# Supply_DDS.net
KiCad netlist of a schematic drawn in Altium Designer
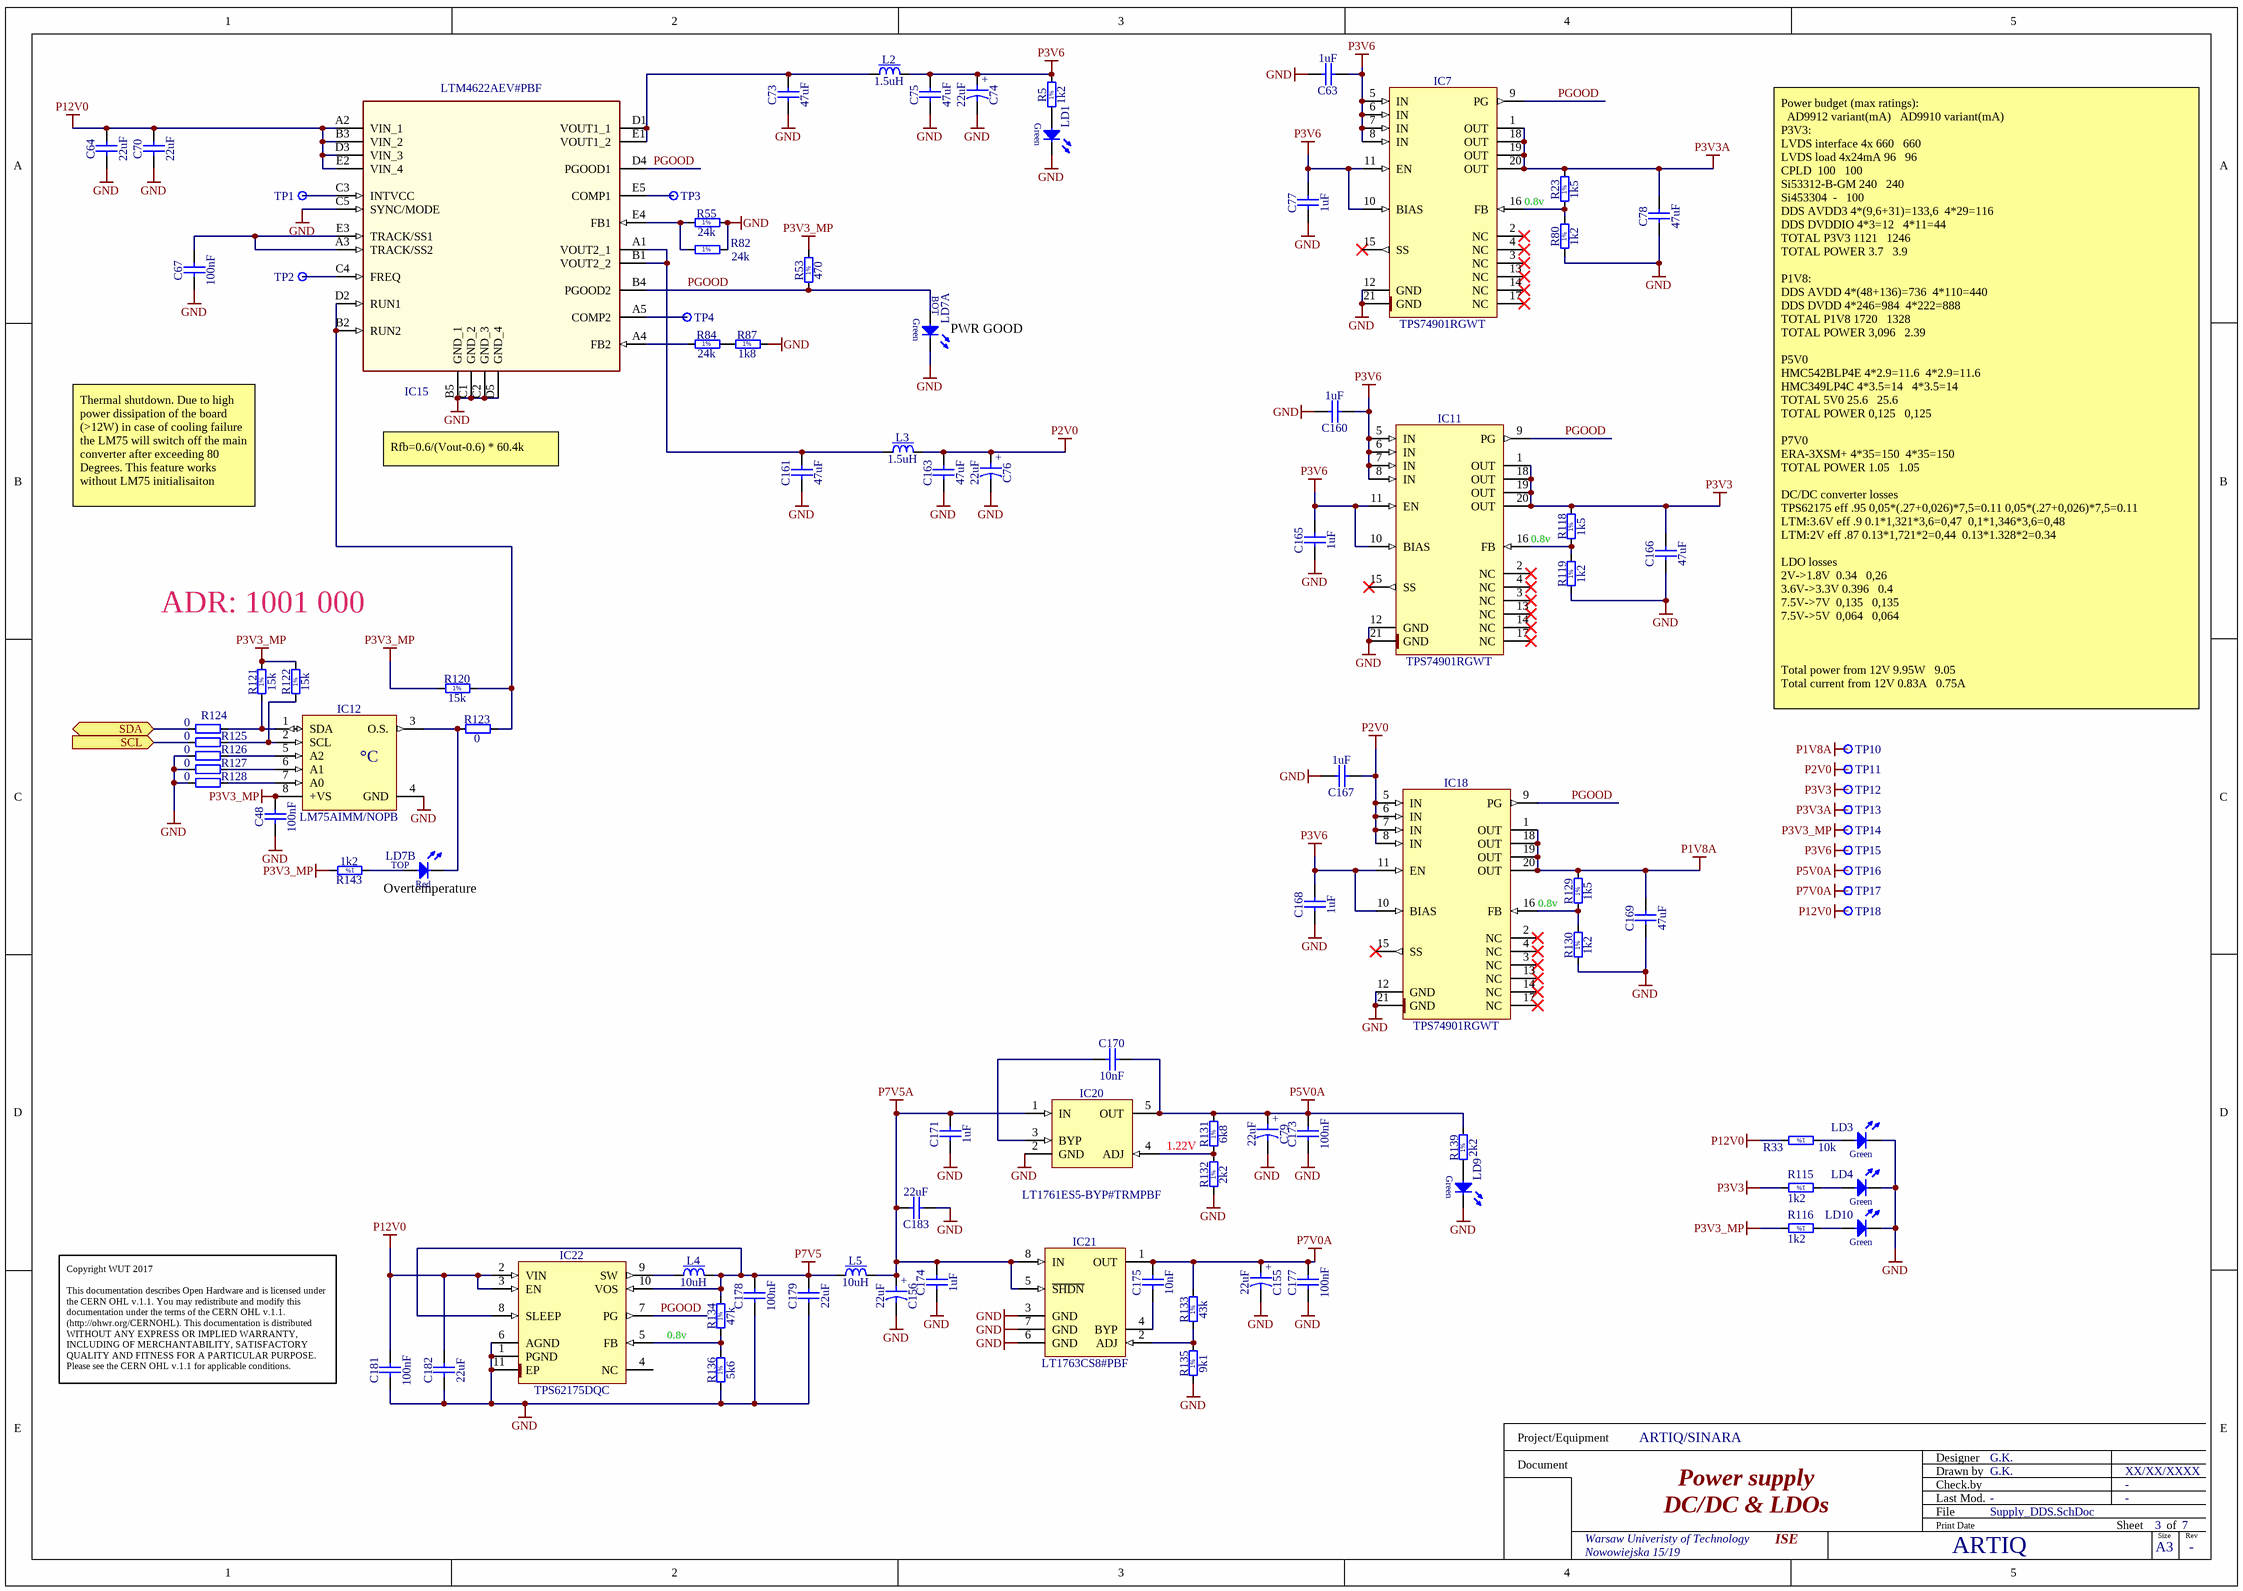
[diagram p0: Supply_DDS.SchDoc]

(export (version "E")
  (design (tool "Eeschema 10.0.6"))
  (components
    (comp (ref "C48")
      (value "100nF")
      (footprint "CAPC1005X55N")
      (description "Non-polarised capacitor")
      (fields (field (name "PART NUMBER") "CC0402_100NF_16V_10%_X5R") (field (name "VOLTAGE") "16V"))
      (libsource (lib "Capacitors") (part "Capacitor - non polarized"))
    )
    (comp (ref "C63")
      (value "1uF")
      (footprint "CAPC1005X55N")
      (description "Non-polarised capacitor")
      (fields (field (name "PART NUMBER") "CC0402_1UF_16V_10%_X5R") (field (name "VOLTAGE") "16V"))
      (libsource (lib "Capacitors") (part "Capacitor - non polarized"))
    )
    (comp (ref "C64")
      (value "22uF")
      (footprint "CAPC2012X135N")
      (description "Non-polarised capacitor")
      (fields (field (name "PART NUMBER") "CC0805_22UF_16V_10%_X5R") (field (name "VOLTAGE") "16V"))
      (libsource (lib "Capacitors") (part "Capacitor - non polarized"))
    )
    (comp (ref "C67")
      (value "100nF")
      (footprint "CAPC1005X55N")
      (description "Non-polarised capacitor")
      (fields (field (name "PART NUMBER") "CC0402_100NF_16V_10%_X5R") (field (name "VOLTAGE") "16V"))
      (libsource (lib "Capacitors") (part "Capacitor - non polarized"))
    )
    (comp (ref "C70")
      (value "22uF")
      (footprint "CAPC2012X135N")
      (description "Non-polarised capacitor")
      (fields (field (name "PART NUMBER") "CC0805_22UF_16V_10%_X5R") (field (name "VOLTAGE") "16V"))
      (libsource (lib "Capacitors") (part "Capacitor - non polarized"))
    )
    (comp (ref "C73")
      (value "47uF")
      (footprint "CAPC3225X270N")
      (description "Non-polarised capacitor")
      (fields (field (name "PART NUMBER") "CC1210_47UF_10V_20%_X5R") (field (name "VOLTAGE") "10V"))
      (libsource (lib "Capacitors") (part "Capacitor - non polarized"))
    )
    (comp (ref "C74")
      (value "22uF")
      (footprint "CAPMP3528X210N")
      (description "Polarised capacitor")
      (fields (field (name "PART NUMBER") "CTE3528-21_22UF_10V_10%_LESR0700") (field (name "VOLTAGE") "10V"))
      (libsource (lib "Capacitors") (part "Capacitor - polarized"))
    )
    (comp (ref "C75")
      (value "47uF")
      (footprint "CAPC3225X270N")
      (description "Non-polarised capacitor")
      (fields (field (name "PART NUMBER") "CC1210_47UF_10V_20%_X5R") (field (name "VOLTAGE") "10V"))
      (libsource (lib "Capacitors") (part "Capacitor - non polarized"))
    )
    (comp (ref "C76")
      (value "22uF")
      (footprint "CAPMP3528X210N")
      (description "Polarised capacitor")
      (fields (field (name "PART NUMBER") "CTE3528-21_22UF_10V_10%_LESR0700") (field (name "VOLTAGE") "10V"))
      (libsource (lib "Capacitors") (part "Capacitor - polarized"))
    )
    (comp (ref "C77")
      (value "1uF")
      (footprint "CAPC1005X55N")
      (description "Non-polarised capacitor")
      (fields (field (name "PART NUMBER") "CC0402_1UF_16V_10%_X5R") (field (name "VOLTAGE") "16V"))
      (libsource (lib "Capacitors") (part "Capacitor - non polarized"))
    )
    (comp (ref "C78")
      (value "47uF")
      (footprint "CAPC3225X270N")
      (description "Non-polarised capacitor")
      (fields (field (name "PART NUMBER") "CC1210_47UF_10V_20%_X5R") (field (name "VOLTAGE") "10V"))
      (libsource (lib "Capacitors") (part "Capacitor - non polarized"))
    )
    (comp (ref "C79")
      (value "22uF")
      (footprint "CAPMP3528X210N")
      (description "Polarised capacitor")
      (fields (field (name "PART NUMBER") "CTE3528-21_22UF_10V_10%_LESR0700") (field (name "VOLTAGE") "10V"))
      (libsource (lib "Capacitors") (part "Capacitor - polarized"))
    )
    (comp (ref "C155")
      (value "22uF")
      (footprint "CAPMP3528X210N")
      (description "Polarised capacitor")
      (fields (field (name "PART NUMBER") "CTE3528-21_22UF_10V_10%_LESR0700") (field (name "VOLTAGE") "10V"))
      (libsource (lib "Capacitors") (part "Capacitor - polarized"))
    )
    (comp (ref "C156")
      (value "22uF")
      (footprint "CAPMP3528X210N")
      (description "Polarised capacitor")
      (fields (field (name "PART NUMBER") "CTE3528-21_22UF_10V_10%_LESR0700") (field (name "VOLTAGE") "10V"))
      (libsource (lib "Capacitors") (part "Capacitor - polarized"))
    )
    (comp (ref "C160")
      (value "1uF")
      (footprint "CAPC1005X55N")
      (description "Non-polarised capacitor")
      (fields (field (name "PART NUMBER") "CC0402_1UF_16V_10%_X5R") (field (name "VOLTAGE") "16V"))
      (libsource (lib "Capacitors") (part "Capacitor - non polarized"))
    )
    (comp (ref "C161")
      (value "47uF")
      (footprint "CAPC3225X270N")
      (description "Non-polarised capacitor")
      (fields (field (name "PART NUMBER") "CC1210_47UF_10V_20%_X5R") (field (name "VOLTAGE") "10V"))
      (libsource (lib "Capacitors") (part "Capacitor - non polarized"))
    )
    (comp (ref "C163")
      (value "47uF")
      (footprint "CAPC3225X270N")
      (description "Non-polarised capacitor")
      (fields (field (name "PART NUMBER") "CC1210_47UF_10V_20%_X5R") (field (name "VOLTAGE") "10V"))
      (libsource (lib "Capacitors") (part "Capacitor - non polarized"))
    )
    (comp (ref "C165")
      (value "1uF")
      (footprint "CAPC1005X55N")
      (description "Non-polarised capacitor")
      (fields (field (name "PART NUMBER") "CC0402_1UF_16V_10%_X5R") (field (name "VOLTAGE") "16V"))
      (libsource (lib "Capacitors") (part "Capacitor - non polarized"))
    )
    (comp (ref "C166")
      (value "47uF")
      (footprint "CAPC3225X270N")
      (description "Non-polarised capacitor")
      (fields (field (name "PART NUMBER") "CC1210_47UF_10V_20%_X5R") (field (name "VOLTAGE") "10V"))
      (libsource (lib "Capacitors") (part "Capacitor - non polarized"))
    )
    (comp (ref "C167")
      (value "1uF")
      (footprint "CAPC1005X55N")
      (description "Non-polarised capacitor")
      (fields (field (name "PART NUMBER") "CC0402_1UF_16V_10%_X5R") (field (name "VOLTAGE") "16V"))
      (libsource (lib "Capacitors") (part "Capacitor - non polarized"))
    )
    (comp (ref "C168")
      (value "1uF")
      (footprint "CAPC1005X55N")
      (description "Non-polarised capacitor")
      (fields (field (name "PART NUMBER") "CC0402_1UF_16V_10%_X5R") (field (name "VOLTAGE") "16V"))
      (libsource (lib "Capacitors") (part "Capacitor - non polarized"))
    )
    (comp (ref "C169")
      (value "47uF")
      (footprint "CAPC3225X270N")
      (description "Non-polarised capacitor")
      (fields (field (name "PART NUMBER") "CC1210_47UF_10V_20%_X5R") (field (name "VOLTAGE") "10V"))
      (libsource (lib "Capacitors") (part "Capacitor - non polarized"))
    )
    (comp (ref "C170")
      (value "10nF")
      (footprint "CAPC1005X55N")
      (description "Non-polarised capacitor")
      (fields (field (name "PART NUMBER") "CC0402_10NF_16V_10%_X7R") (field (name "VOLTAGE") "16V"))
      (libsource (lib "Capacitors") (part "Capacitor - non polarized"))
    )
    (comp (ref "C171")
      (value "1uF")
      (footprint "CAPC1005X55N")
      (description "Non-polarised capacitor")
      (fields (field (name "PART NUMBER") "CC0402_1UF_16V_10%_X5R") (field (name "VOLTAGE") "16V"))
      (libsource (lib "Capacitors") (part "Capacitor - non polarized"))
    )
    (comp (ref "C173")
      (value "100nF")
      (footprint "CAPC1005X55N")
      (description "Non-polarised capacitor")
      (fields (field (name "PART NUMBER") "CC0402_100NF_16V_10%_X5R") (field (name "VOLTAGE") "16V"))
      (libsource (lib "Capacitors") (part "Capacitor - non polarized"))
    )
    (comp (ref "C174")
      (value "1uF")
      (footprint "CAPC1005X55N")
      (description "Non-polarised capacitor")
      (fields (field (name "PART NUMBER") "CC0402_1UF_16V_10%_X5R") (field (name "VOLTAGE") "16V"))
      (libsource (lib "Capacitors") (part "Capacitor - non polarized"))
    )
    (comp (ref "C175")
      (value "10nF")
      (footprint "CAPC1005X55N")
      (description "Non-polarised capacitor")
      (fields (field (name "PART NUMBER") "CC0402_10NF_16V_10%_X7R") (field (name "VOLTAGE") "16V"))
      (libsource (lib "Capacitors") (part "Capacitor - non polarized"))
    )
    (comp (ref "C177")
      (value "100nF")
      (footprint "CAPC1005X55N")
      (description "Non-polarised capacitor")
      (fields (field (name "PART NUMBER") "CC0402_100NF_16V_10%_X5R") (field (name "VOLTAGE") "16V"))
      (libsource (lib "Capacitors") (part "Capacitor - non polarized"))
    )
    (comp (ref "C178")
      (value "100nF")
      (footprint "CAPC1005X55N")
      (description "Non-polarised capacitor")
      (fields (field (name "PART NUMBER") "CC0402_100NF_16V_10%_X5R") (field (name "VOLTAGE") "16V"))
      (libsource (lib "Capacitors") (part "Capacitor - non polarized"))
    )
    (comp (ref "C179")
      (value "22uF")
      (footprint "CAPC2012X135N")
      (description "Non-polarised capacitor")
      (fields (field (name "PART NUMBER") "CC0805_22UF_16V_10%_X5R") (field (name "VOLTAGE") "16V"))
      (libsource (lib "Capacitors") (part "Capacitor - non polarized"))
    )
    (comp (ref "C181")
      (value "100nF")
      (footprint "CAPC1005X55N")
      (description "Non-polarised capacitor")
      (fields (field (name "PART NUMBER") "CC0402_100NF_16V_10%_X5R") (field (name "VOLTAGE") "16V"))
      (libsource (lib "Capacitors") (part "Capacitor - non polarized"))
    )
    (comp (ref "C182")
      (value "22uF")
      (footprint "CAPC2012X135N")
      (description "Non-polarised capacitor")
      (fields (field (name "PART NUMBER") "CC0805_22UF_16V_10%_X5R") (field (name "VOLTAGE") "16V"))
      (libsource (lib "Capacitors") (part "Capacitor - non polarized"))
    )
    (comp (ref "C183")
      (value "22uF")
      (footprint "CAPC2012X135N")
      (description "Non-polarised capacitor")
      (fields (field (name "PART NUMBER") "CC0805_22UF_16V_10%_X5R") (field (name "VOLTAGE") "16V"))
      (libsource (lib "Capacitors") (part "Capacitor - non polarized"))
    )
    (comp (ref "IC7")
      (value "TPS74901RGWT")
      (footprint "QFN65P500X500X100-21N-S325")
      (description "3A, 0.8 to 3.6V Adjustable Low-Dropout Linear Regulator with Programmable Soft-Start")
      (fields (field (name "MANUFACTURER") "TEXAS INSTRUMENTS"))
      (libsource (lib "ICs And Semiconductors") (part "TPS74901RGWT"))
    )
    (comp (ref "IC11")
      (value "TPS74901RGWT")
      (footprint "QFN65P500X500X100-21N-S325")
      (description "3A, 0.8 to 3.6V Adjustable Low-Dropout Linear Regulator with Programmable Soft-Start")
      (fields (field (name "MANUFACTURER") "TEXAS INSTRUMENTS"))
      (libsource (lib "ICs And Semiconductors") (part "TPS74901RGWT"))
    )
    (comp (ref "IC12")
      (value "LM75AIMM/NOPB")
      (footprint "SOP65P490X109-8N")
      (description "Digital Temperature Sensor and Thermal Watchdog with Two-Wire Interface")
      (fields (field (name "MANUFACTURER") "TEXAS INSTRUMENTS"))
      (libsource (lib "ICs And Semiconductors") (part "LM75"))
    )
    (comp (ref "IC15")
      (value "LTM4622AEV#PBF")
      (footprint "LGA25C127P5X5_625X625X190")
      (description "Dual Ultrathin 2A or Single 4A, 3.6V to 20V, 1.5V to 12V   Step-Down DC/DC μModule Regulator")
      (fields (field (name "MANUFACTURER") "LINEAR TECHNOLOGY"))
      (libsource (lib "LIBRARY_SCH") (part "PM_LTM4622"))
    )
    (comp (ref "IC18")
      (value "TPS74901RGWT")
      (footprint "QFN65P500X500X100-21N-S325")
      (description "3A, 0.8 to 3.6V Adjustable Low-Dropout Linear Regulator with Programmable Soft-Start")
      (fields (field (name "MANUFACTURER") "TEXAS INSTRUMENTS"))
      (libsource (lib "ICs And Semiconductors") (part "TPS74901RGWT"))
    )
    (comp (ref "IC20")
      (value "LT1761ES5-BYP#TRMPBF")
      (footprint "SOT95P280X100-5N")
      (description "100mA, Low Noise, LDO Micropower Adjustable Regulator in SOT-23")
      (fields (field (name "MANUFACTURER") "LINEAR TECHNOLOGY"))
      (libsource (lib "ICs And Semiconductors") (part "LT1761-BYP"))
    )
    (comp (ref "IC21")
      (value "LT1763CS8#PBF")
      (footprint "SOIC127P600X175-8N")
      (description "1.22V to 20V 500mA, Low Noise, LDO Adjustable Micropower Regulator")
      (fields (field (name "MANUFACTURER") "LINEAR TECHNOLOGY"))
      (libsource (lib "ICs And Semiconductors") (part "LT1763xS8"))
    )
    (comp (ref "IC22")
      (value "TPS62175DQC")
      (footprint "SON50P200X300X80-11N-R94X250")
      (description "4.75-28VDC to 1-6VDC, 500mA Step-Down Converter With Sleep Mode")
      (fields (field (name "MANUFACTURER") "TEXAS INSTRUMENTS"))
      (libsource (lib "ICs And Semiconductors") (part "TPS62175"))
    )
    (comp (ref "L2")
      (value "1.5uH")
      (footprint "IND_TDK_SPM6530")
      (description "Inductor With Core")
      (fields (field (name "PART NUMBER") "IND_1.5UH_20%_TDK_SPM6530") (field (name "POWER") "11A"))
      (libsource (lib "Inductors & Transformers") (part "Inductor With Magnetic core"))
    )
    (comp (ref "L3")
      (value "1.5uH")
      (footprint "IND_TDK_SPM6530")
      (description "Inductor With Core")
      (fields (field (name "PART NUMBER") "IND_1.5UH_20%_TDK_SPM6530") (field (name "POWER") "11A"))
      (libsource (lib "Inductors & Transformers") (part "Inductor With Magnetic core"))
    )
    (comp (ref "L4")
      (value "10uH")
      (footprint "IND_MURATA-PS_8400")
      (description "Inductor With Core")
      (fields (field (name "PART NUMBER") "IND_10UH_10%_MURATA-PS_8400") (field (name "POWER") "950mA"))
      (libsource (lib "Inductors & Transformers") (part "Inductor With Magnetic core"))
    )
    (comp (ref "L5")
      (value "10uH")
      (footprint "IND_MURATA-PS_8400")
      (description "Inductor With Core")
      (fields (field (name "PART NUMBER") "IND_10UH_10%_MURATA-PS_8400") (field (name "POWER") "950mA"))
      (libsource (lib "Inductors & Transformers") (part "Inductor With Magnetic core"))
    )
    (comp (ref "LD1")
      (value "Green")
      (footprint "LED_KINGBRIGHT_KPH-1608CGCKr")
      (description "Green 0603")
      (fields
        (field (name "PART NUMBER") "LED_KINGBRIGHT_KPH-1608CGCK")
        (field (name "MANUFACTURER") "KINGBRIGHT")
      )
      (libsource (lib "LIBRARY_SCH") (part "LED_0603_Green"))
    )
    (comp (ref "LD3")
      (value "Green")
      (footprint "LED_KINGBRIGHT_KPH-1608CGCKr")
      (description "Green 0603")
      (fields
        (field (name "PART NUMBER") "LED_KINGBRIGHT_KPH-1608CGCK")
        (field (name "MANUFACTURER") "KINGBRIGHT")
      )
      (libsource (lib "LIBRARY_SCH") (part "LED_0603_Green"))
    )
    (comp (ref "LD4")
      (value "Green")
      (footprint "LED_KINGBRIGHT_KPH-1608CGCKr")
      (description "Green 0603")
      (fields
        (field (name "PART NUMBER") "LED_KINGBRIGHT_KPH-1608CGCK")
        (field (name "MANUFACTURER") "KINGBRIGHT")
      )
      (libsource (lib "LIBRARY_SCH") (part "LED_0603_Green"))
    )
    (comp (ref "LD7")
      (value "Red/Green")
      (footprint "LED_DIALIGHT_553-0112-200F")
      (description "2x LED  Botom Green, Top Red")
      (fields
        (field (name "PART NUMBER") "LED_DIALIGHT_553-0112-200F")
        (field (name "MANUFACTURER") "DIALIGHT")
      )
      (libsource (lib "ICs And Semiconductors") (part "LED x2 G-1C2A-BOT_R-3C4A-TOP"))
    )
    (comp (ref "LD9")
      (value "Green")
      (footprint "LED_KINGBRIGHT_KPH-1608CGCKr")
      (description "Green 0603")
      (fields
        (field (name "PART NUMBER") "LED_KINGBRIGHT_KPH-1608CGCK")
        (field (name "MANUFACTURER") "KINGBRIGHT")
      )
      (libsource (lib "LIBRARY_SCH") (part "LED_0603_Green"))
    )
    (comp (ref "LD10")
      (value "Green")
      (footprint "LED_KINGBRIGHT_KPH-1608CGCKr")
      (description "Green 0603")
      (fields
        (field (name "PART NUMBER") "LED_KINGBRIGHT_KPH-1608CGCK")
        (field (name "MANUFACTURER") "KINGBRIGHT")
      )
      (libsource (lib "LIBRARY_SCH") (part "LED_0603_Green"))
    )
    (comp (ref "R5")
      (value "1k2")
      (footprint "RESC1608X55N")
      (description "Resistor - 1%")
      (fields (field (name "PART NUMBER") "R0603_1K2_1%_0.1W_100PPM") (field (name "POWER") "0.1W"))
      (libsource (lib "Resistors") (part "Resistor - 1%"))
    )
    (comp (ref "R23")
      (value "1k5")
      (footprint "RESC1608X55N")
      (description "Resistor - 1%")
      (fields (field (name "PART NUMBER") "R0603_1K5_1%_0.1W_100PPM") (field (name "POWER") "0.1W"))
      (libsource (lib "Resistors") (part "Resistor - 1%"))
    )
    (comp (ref "R33")
      (value "10k")
      (footprint "RESC1005X40N")
      (description "Resistor - 1%")
      (fields (field (name "PART NUMBER") "R0402_10K_1%_0.0625W_100PPM") (field (name "POWER") "0.0625W"))
      (libsource (lib "Resistors") (part "Resistor - 1%"))
    )
    (comp (ref "R53")
      (value "470")
      (footprint "RESC1005X40N")
      (description "Resistor - 1%")
      (fields (field (name "PART NUMBER") "R0402_470R_1%_0.0625W_100PPM") (field (name "POWER") "0.0625W"))
      (libsource (lib "Resistors") (part "Resistor - 1%"))
    )
    (comp (ref "R55")
      (value "24k")
      (footprint "RESC1608X55N")
      (description "Resistor - 1%")
      (fields (field (name "PART NUMBER") "R0603_24K_1%_0.1W_100PPM") (field (name "POWER") "0.1W"))
      (libsource (lib "Resistors") (part "Resistor - 1%"))
    )
    (comp (ref "R80")
      (value "1k2")
      (footprint "RESC1608X55N")
      (description "Resistor - 1%")
      (fields (field (name "PART NUMBER") "R0603_1K2_1%_0.1W_100PPM") (field (name "POWER") "0.1W"))
      (libsource (lib "Resistors") (part "Resistor - 1%"))
    )
    (comp (ref "R82")
      (value "24k")
      (footprint "RESC1608X55N")
      (description "Resistor - 1%")
      (fields (field (name "PART NUMBER") "R0603_24K_1%_0.1W_100PPM") (field (name "POWER") "0.1W"))
      (libsource (lib "Resistors") (part "Resistor - 1%"))
    )
    (comp (ref "R84")
      (value "24k")
      (footprint "RESC1608X55N")
      (description "Resistor - 1%")
      (fields (field (name "PART NUMBER") "R0603_24K_1%_0.1W_100PPM") (field (name "POWER") "0.1W"))
      (libsource (lib "Resistors") (part "Resistor - 1%"))
    )
    (comp (ref "R87")
      (value "1k8")
      (footprint "RESC1608X55N")
      (description "Resistor - 1%")
      (fields (field (name "PART NUMBER") "R0603_1K8_1%_0.1W_100PPM") (field (name "POWER") "0.1W"))
      (libsource (lib "Resistors") (part "Resistor - 1%"))
    )
    (comp (ref "R115")
      (value "1k2")
      (footprint "RESC1608X55N")
      (description "Resistor - 1%")
      (fields (field (name "PART NUMBER") "R0603_1K2_1%_0.1W_100PPM") (field (name "POWER") "0.1W"))
      (libsource (lib "Resistors") (part "Resistor - 1%"))
    )
    (comp (ref "R116")
      (value "1k2")
      (footprint "RESC1608X55N")
      (description "Resistor - 1%")
      (fields (field (name "PART NUMBER") "R0603_1K2_1%_0.1W_100PPM") (field (name "POWER") "0.1W"))
      (libsource (lib "Resistors") (part "Resistor - 1%"))
    )
    (comp (ref "R118")
      (value "1k5")
      (footprint "RESC1608X55N")
      (description "Resistor - 1%")
      (fields (field (name "PART NUMBER") "R0603_1K5_1%_0.1W_100PPM") (field (name "POWER") "0.1W"))
      (libsource (lib "Resistors") (part "Resistor - 1%"))
    )
    (comp (ref "R119")
      (value "1k2")
      (footprint "RESC1608X55N")
      (description "Resistor - 1%")
      (fields (field (name "PART NUMBER") "R0603_1K2_1%_0.1W_100PPM") (field (name "POWER") "0.1W"))
      (libsource (lib "Resistors") (part "Resistor - 1%"))
    )
    (comp (ref "R120")
      (value "15k")
      (footprint "RESC1608X55N")
      (description "Resistor - 1%")
      (fields (field (name "PART NUMBER") "R0603_15K_1%_0.1W_100PPM") (field (name "POWER") "0.1W"))
      (libsource (lib "Resistors") (part "Resistor - 1%"))
    )
    (comp (ref "R121")
      (value "15k")
      (footprint "RESC1608X55N")
      (description "Resistor - 1%")
      (fields (field (name "PART NUMBER") "R0603_15K_1%_0.1W_100PPM") (field (name "POWER") "0.1W"))
      (libsource (lib "Resistors") (part "Resistor - 1%"))
    )
    (comp (ref "R122")
      (value "15k")
      (footprint "RESC1608X55N")
      (description "Resistor - 1%")
      (fields (field (name "PART NUMBER") "R0603_15K_1%_0.1W_100PPM") (field (name "POWER") "0.1W"))
      (libsource (lib "Resistors") (part "Resistor - 1%"))
    )
    (comp (ref "R123")
      (value "0")
      (footprint "RESC1005X40N")
      (description "Resistor")
      (fields (field (name "PART NUMBER") "R0402_0R_JUMPER") (field (name "MANUFACTURER") "GENERIC"))
      (libsource (lib "Resistors") (part "Resistor"))
    )
    (comp (ref "R124")
      (value "0")
      (footprint "RESC1005X40N")
      (description "Resistor")
      (fields (field (name "PART NUMBER") "R0402_0R_JUMPER") (field (name "MANUFACTURER") "GENERIC"))
      (libsource (lib "Resistors") (part "Resistor"))
    )
    (comp (ref "R125")
      (value "0")
      (footprint "RESC1005X40N")
      (description "Resistor")
      (fields (field (name "PART NUMBER") "R0402_0R_JUMPER") (field (name "MANUFACTURER") "GENERIC"))
      (libsource (lib "Resistors") (part "Resistor"))
    )
    (comp (ref "R126")
      (value "0")
      (footprint "RESC1005X40N")
      (description "Resistor")
      (fields (field (name "PART NUMBER") "R0402_0R_JUMPER") (field (name "MANUFACTURER") "GENERIC"))
      (libsource (lib "Resistors") (part "Resistor"))
    )
    (comp (ref "R127")
      (value "0")
      (footprint "RESC1005X40N")
      (description "Resistor")
      (fields (field (name "PART NUMBER") "R0402_0R_JUMPER") (field (name "MANUFACTURER") "GENERIC"))
      (libsource (lib "Resistors") (part "Resistor"))
    )
    (comp (ref "R128")
      (value "0")
      (footprint "RESC1005X40N")
      (description "Resistor")
      (fields (field (name "PART NUMBER") "R0402_0R_JUMPER") (field (name "MANUFACTURER") "GENERIC"))
      (libsource (lib "Resistors") (part "Resistor"))
    )
    (comp (ref "R129")
      (value "1k5")
      (footprint "RESC1608X55N")
      (description "Resistor - 1%")
      (fields (field (name "PART NUMBER") "R0603_1K5_1%_0.1W_100PPM") (field (name "POWER") "0.1W"))
      (libsource (lib "Resistors") (part "Resistor - 1%"))
    )
    (comp (ref "R130")
      (value "1k2")
      (footprint "RESC1608X55N")
      (description "Resistor - 1%")
      (fields (field (name "PART NUMBER") "R0603_1K2_1%_0.1W_100PPM") (field (name "POWER") "0.1W"))
      (libsource (lib "Resistors") (part "Resistor - 1%"))
    )
    (comp (ref "R131")
      (value "6k8")
      (footprint "RESC1608X55N")
      (description "Resistor - 1%")
      (fields (field (name "PART NUMBER") "R0603_6K8_1%_0.1W_100PPM") (field (name "POWER") "0.1W"))
      (libsource (lib "Resistors") (part "Resistor - 1%"))
    )
    (comp (ref "R132")
      (value "2k2")
      (footprint "RESC1608X55N")
      (description "Resistor - 1%")
      (fields (field (name "PART NUMBER") "R0603_2K2_1%_0.1W_100PPM") (field (name "POWER") "0.1W"))
      (libsource (lib "Resistors") (part "Resistor - 1%"))
    )
    (comp (ref "R133")
      (value "43k")
      (footprint "RESC1608X55N")
      (description "Resistor - 1%")
      (fields (field (name "PART NUMBER") "R0603_43K_1%_0.1W_100PPM") (field (name "POWER") "0.1W"))
      (libsource (lib "Resistors") (part "Resistor - 1%"))
    )
    (comp (ref "R134")
      (value "47k")
      (footprint "RESC1608X55N")
      (description "Resistor - 1%")
      (fields (field (name "PART NUMBER") "R0603_47K_1%_0.1W_100PPM") (field (name "POWER") "0.1W"))
      (libsource (lib "Resistors") (part "Resistor - 1%"))
    )
    (comp (ref "R135")
      (value "9k1")
      (footprint "RESC1608X55N")
      (description "Resistor - 1%")
      (fields (field (name "PART NUMBER") "R0603_9K1_1%_0.1W_100PPM") (field (name "POWER") "0.1W"))
      (libsource (lib "Resistors") (part "Resistor - 1%"))
    )
    (comp (ref "R136")
      (value "5k6")
      (footprint "RESC1608X55N")
      (description "Resistor - 1%")
      (fields (field (name "PART NUMBER") "R0603_5K6_1%_0.1W_100PPM") (field (name "POWER") "0.1W"))
      (libsource (lib "Resistors") (part "Resistor - 1%"))
    )
    (comp (ref "R139")
      (value "2k2")
      (footprint "RESC1608X55N")
      (description "Resistor - 1%")
      (fields (field (name "PART NUMBER") "R0603_2K2_1%_0.1W_100PPM") (field (name "POWER") "0.1W"))
      (libsource (lib "Resistors") (part "Resistor - 1%"))
    )
    (comp (ref "R143")
      (value "1k2")
      (footprint "RESC1608X55N")
      (description "Resistor - 1%")
      (fields (field (name "PART NUMBER") "R0603_1K2_1%_0.1W_100PPM") (field (name "POWER") "0.1W"))
      (libsource (lib "Resistors") (part "Resistor - 1%"))
    )
    (comp (ref "TP1")
      (value "Test Point")
      (footprint "TPS127")
      (fields (field (name "PART NUMBER") "SMD_PAD_1.27X1.27MM"))
      (libsource (lib "Eletro-mechanical") (part "Test Point"))
    )
    (comp (ref "TP2")
      (value "Test Point")
      (footprint "TPS127")
      (fields (field (name "PART NUMBER") "SMD_PAD_1.27X1.27MM"))
      (libsource (lib "Eletro-mechanical") (part "Test Point"))
    )
    (comp (ref "TP3")
      (value "Test Point")
      (footprint "TPS127")
      (fields (field (name "PART NUMBER") "SMD_PAD_1.27X1.27MM"))
      (libsource (lib "Eletro-mechanical") (part "Test Point"))
    )
    (comp (ref "TP4")
      (value "Test Point")
      (footprint "TPS127")
      (fields (field (name "PART NUMBER") "SMD_PAD_1.27X1.27MM"))
      (libsource (lib "Eletro-mechanical") (part "Test Point"))
    )
    (comp (ref "TP10")
      (value "Test Point")
      (footprint "TPS127")
      (fields (field (name "PART NUMBER") "SMD_PAD_1.27X1.27MM"))
      (libsource (lib "Eletro-mechanical") (part "Test Point"))
    )
    (comp (ref "TP11")
      (value "Test Point")
      (footprint "TPS127")
      (fields (field (name "PART NUMBER") "SMD_PAD_1.27X1.27MM"))
      (libsource (lib "Eletro-mechanical") (part "Test Point"))
    )
    (comp (ref "TP12")
      (value "Test Point")
      (footprint "TPS127")
      (fields (field (name "PART NUMBER") "SMD_PAD_1.27X1.27MM"))
      (libsource (lib "Eletro-mechanical") (part "Test Point"))
    )
    (comp (ref "TP13")
      (value "Test Point")
      (footprint "TPS127")
      (fields (field (name "PART NUMBER") "SMD_PAD_1.27X1.27MM"))
      (libsource (lib "Eletro-mechanical") (part "Test Point"))
    )
    (comp (ref "TP14")
      (value "Test Point")
      (footprint "TPS127")
      (fields (field (name "PART NUMBER") "SMD_PAD_1.27X1.27MM"))
      (libsource (lib "Eletro-mechanical") (part "Test Point"))
    )
    (comp (ref "TP15")
      (value "Test Point")
      (footprint "TPS127")
      (fields (field (name "PART NUMBER") "SMD_PAD_1.27X1.27MM"))
      (libsource (lib "Eletro-mechanical") (part "Test Point"))
    )
    (comp (ref "TP16")
      (value "Test Point")
      (footprint "TPS127")
      (fields (field (name "PART NUMBER") "SMD_PAD_1.27X1.27MM"))
      (libsource (lib "Eletro-mechanical") (part "Test Point"))
    )
    (comp (ref "TP17")
      (value "Test Point")
      (footprint "TPS127")
      (fields (field (name "PART NUMBER") "SMD_PAD_1.27X1.27MM"))
      (libsource (lib "Eletro-mechanical") (part "Test Point"))
    )
    (comp (ref "TP18")
      (value "Test Point")
      (footprint "TPS127")
      (fields (field (name "PART NUMBER") "SMD_PAD_1.27X1.27MM"))
      (libsource (lib "Eletro-mechanical") (part "Test Point"))
    )
  )
  (nets
    (net (code "1") (name "/PGOOD") (class "Default")
      (node (ref "IC11") (pin "9") (pinfunction "PG_9") (pintype "output"))
      (node (ref "IC15") (pin "B4") (pinfunction "PGOOD2_B4") (pintype "open_collector"))
      (node (ref "IC15") (pin "D4") (pinfunction "PGOOD1_D4") (pintype "open_collector"))
      (node (ref "IC18") (pin "9") (pinfunction "PG_9") (pintype "output"))
      (node (ref "IC22") (pin "7") (pinfunction "PG_7") (pintype "output"))
      (node (ref "IC7") (pin "9") (pinfunction "PG_9") (pintype "output"))
      (node (ref "LD7") (pin "2") (pinfunction "A_2") (pintype "passive"))
      (node (ref "R53") (pin "1") (pinfunction "1_1") (pintype "passive"))
    )
    (net (code "2") (name "/SCL") (class "Default")
      (node (ref "R125") (pin "1") (pinfunction "1_1") (pintype "passive"))
    )
    (net (code "3") (name "/SDA") (class "Default")
      (node (ref "R124") (pin "1") (pinfunction "1_1") (pintype "passive"))
    )
    (net (code "4") (name "GND") (class "Default")
      (node (ref "C155") (pin "2") (pinfunction "2_2") (pintype "passive"))
      (node (ref "C156") (pin "2") (pinfunction "2_2") (pintype "passive"))
      (node (ref "C160") (pin "2") (pinfunction "2_2") (pintype "passive"))
      (node (ref "C161") (pin "1") (pinfunction "1_1") (pintype "passive"))
      (node (ref "C163") (pin "1") (pinfunction "1_1") (pintype "passive"))
      (node (ref "C165") (pin "1") (pinfunction "1_1") (pintype "passive"))
      (node (ref "C166") (pin "1") (pinfunction "1_1") (pintype "passive"))
      (node (ref "C167") (pin "2") (pinfunction "2_2") (pintype "passive"))
      (node (ref "C168") (pin "1") (pinfunction "1_1") (pintype "passive"))
      (node (ref "C169") (pin "1") (pinfunction "1_1") (pintype "passive"))
      (node (ref "C171") (pin "1") (pinfunction "1_1") (pintype "passive"))
      (node (ref "C173") (pin "1") (pinfunction "1_1") (pintype "passive"))
      (node (ref "C174") (pin "1") (pinfunction "1_1") (pintype "passive"))
      (node (ref "C177") (pin "1") (pinfunction "1_1") (pintype "passive"))
      (node (ref "C178") (pin "1") (pinfunction "1_1") (pintype "passive"))
      (node (ref "C179") (pin "1") (pinfunction "1_1") (pintype "passive"))
      (node (ref "C181") (pin "1") (pinfunction "1_1") (pintype "passive"))
      (node (ref "C182") (pin "1") (pinfunction "1_1") (pintype "passive"))
      (node (ref "C183") (pin "1") (pinfunction "1_1") (pintype "passive"))
      (node (ref "C48") (pin "1") (pinfunction "1_1") (pintype "passive"))
      (node (ref "C63") (pin "2") (pinfunction "2_2") (pintype "passive"))
      (node (ref "C64") (pin "1") (pinfunction "1_1") (pintype "passive"))
      (node (ref "C67") (pin "1") (pinfunction "1_1") (pintype "passive"))
      (node (ref "C70") (pin "1") (pinfunction "1_1") (pintype "passive"))
      (node (ref "C73") (pin "1") (pinfunction "1_1") (pintype "passive"))
      (node (ref "C74") (pin "2") (pinfunction "2_2") (pintype "passive"))
      (node (ref "C75") (pin "1") (pinfunction "1_1") (pintype "passive"))
      (node (ref "C76") (pin "2") (pinfunction "2_2") (pintype "passive"))
      (node (ref "C77") (pin "1") (pinfunction "1_1") (pintype "passive"))
      (node (ref "C78") (pin "1") (pinfunction "1_1") (pintype "passive"))
      (node (ref "C79") (pin "2") (pinfunction "2_2") (pintype "passive"))
      (node (ref "IC11") (pin "12") (pinfunction "GND_12") (pintype "power_in"))
      (node (ref "IC11") (pin "21") (pinfunction "GND_21") (pintype "power_in"))
      (node (ref "IC12") (pin "4") (pinfunction "GND_4") (pintype "power_in"))
      (node (ref "IC15") (pin "B5") (pinfunction "GND_1_B5") (pintype "power_in"))
      (node (ref "IC15") (pin "C1") (pinfunction "GND_2_C1") (pintype "power_in"))
      (node (ref "IC15") (pin "C2") (pinfunction "GND_3_C2") (pintype "power_in"))
      (node (ref "IC15") (pin "C5") (pinfunction "SYNC/MODE_C5") (pintype "input"))
      (node (ref "IC15") (pin "D5") (pinfunction "GND_4_D5") (pintype "power_in"))
      (node (ref "IC18") (pin "12") (pinfunction "GND_12") (pintype "power_in"))
      (node (ref "IC18") (pin "21") (pinfunction "GND_21") (pintype "power_in"))
      (node (ref "IC20") (pin "2") (pinfunction "GND_2") (pintype "power_in"))
      (node (ref "IC21") (pin "3") (pinfunction "GND_3") (pintype "power_in"))
      (node (ref "IC21") (pin "6") (pinfunction "GND_6") (pintype "power_in"))
      (node (ref "IC21") (pin "7") (pinfunction "GND_7") (pintype "power_in"))
      (node (ref "IC22") (pin "1") (pinfunction "PGND_1") (pintype "power_in"))
      (node (ref "IC22") (pin "11") (pinfunction "EP_11") (pintype "power_in"))
      (node (ref "IC22") (pin "6") (pinfunction "AGND_6") (pintype "power_in"))
      (node (ref "IC7") (pin "12") (pinfunction "GND_12") (pintype "power_in"))
      (node (ref "IC7") (pin "21") (pinfunction "GND_21") (pintype "power_in"))
      (node (ref "LD1") (pin "1") (pinfunction "C_1") (pintype "passive"))
      (node (ref "LD10") (pin "1") (pinfunction "C_1") (pintype "passive"))
      (node (ref "LD3") (pin "1") (pinfunction "C_1") (pintype "passive"))
      (node (ref "LD4") (pin "1") (pinfunction "C_1") (pintype "passive"))
      (node (ref "LD7") (pin "1") (pinfunction "C_1") (pintype "passive"))
      (node (ref "LD9") (pin "1") (pinfunction "C_1") (pintype "passive"))
      (node (ref "R119") (pin "1") (pinfunction "1_1") (pintype "passive"))
      (node (ref "R126") (pin "1") (pinfunction "1_1") (pintype "passive"))
      (node (ref "R127") (pin "1") (pinfunction "1_1") (pintype "passive"))
      (node (ref "R128") (pin "1") (pinfunction "1_1") (pintype "passive"))
      (node (ref "R130") (pin "1") (pinfunction "1_1") (pintype "passive"))
      (node (ref "R132") (pin "1") (pinfunction "1_1") (pintype "passive"))
      (node (ref "R135") (pin "1") (pinfunction "1_1") (pintype "passive"))
      (node (ref "R136") (pin "1") (pinfunction "1_1") (pintype "passive"))
      (node (ref "R55") (pin "2") (pinfunction "2_2") (pintype "passive"))
      (node (ref "R80") (pin "1") (pinfunction "1_1") (pintype "passive"))
      (node (ref "R82") (pin "2") (pinfunction "2_2") (pintype "passive"))
      (node (ref "R87") (pin "2") (pinfunction "2_2") (pintype "passive"))
    )
    (net (code "5") (name "Net-(IC7-FB)") (class "Default")
      (node (ref "IC7") (pin "16") (pinfunction "FB_16") (pintype "input"))
      (node (ref "R23") (pin "1") (pinfunction "1_1") (pintype "passive"))
      (node (ref "R80") (pin "2") (pinfunction "2_2") (pintype "passive"))
    )
    (net (code "6") (name "Net-(IC11-FB)") (class "Default")
      (node (ref "IC11") (pin "16") (pinfunction "FB_16") (pintype "input"))
      (node (ref "R118") (pin "1") (pinfunction "1_1") (pintype "passive"))
      (node (ref "R119") (pin "2") (pinfunction "2_2") (pintype "passive"))
    )
    (net (code "7") (name "Net-(IC12-A0)") (class "Default")
      (node (ref "IC12") (pin "7") (pinfunction "A0_7") (pintype "input"))
      (node (ref "R128") (pin "2") (pinfunction "2_2") (pintype "passive"))
    )
    (net (code "8") (name "Net-(IC12-A1)") (class "Default")
      (node (ref "IC12") (pin "6") (pinfunction "A1_6") (pintype "input"))
      (node (ref "R127") (pin "2") (pinfunction "2_2") (pintype "passive"))
    )
    (net (code "9") (name "Net-(IC12-A2)") (class "Default")
      (node (ref "IC12") (pin "5") (pinfunction "A2_5") (pintype "input"))
      (node (ref "R126") (pin "2") (pinfunction "2_2") (pintype "passive"))
    )
    (net (code "10") (name "Net-(IC12-O.S.)") (class "Default")
      (node (ref "IC12") (pin "3") (pinfunction "O.S._3") (pintype "output"))
      (node (ref "LD7") (pin "3") (pinfunction "C_3") (pintype "passive"))
      (node (ref "R123") (pin "1") (pinfunction "1_1") (pintype "passive"))
    )
    (net (code "11") (name "Net-(IC12-SCL)") (class "Default")
      (node (ref "IC12") (pin "2") (pinfunction "SCL_2") (pintype "input"))
      (node (ref "R122") (pin "1") (pinfunction "1_1") (pintype "passive"))
      (node (ref "R125") (pin "2") (pinfunction "2_2") (pintype "passive"))
    )
    (net (code "12") (name "Net-(IC12-SDA)") (class "Default")
      (node (ref "IC12") (pin "1") (pinfunction "SDA_1") (pintype "bidirectional"))
      (node (ref "R121") (pin "1") (pinfunction "1_1") (pintype "passive"))
      (node (ref "R124") (pin "2") (pinfunction "2_2") (pintype "passive"))
    )
    (net (code "13") (name "Net-(IC15-COMP1)") (class "Default")
      (node (ref "IC15") (pin "E5") (pinfunction "COMP1_E5") (pintype "passive"))
      (node (ref "TP3") (pin "1") (pinfunction "1_1") (pintype "bidirectional"))
    )
    (net (code "14") (name "Net-(IC15-COMP2)") (class "Default")
      (node (ref "IC15") (pin "A5") (pinfunction "COMP2_A5") (pintype "passive"))
      (node (ref "TP4") (pin "1") (pinfunction "1_1") (pintype "bidirectional"))
    )
    (net (code "15") (name "Net-(IC15-FB1)") (class "Default")
      (node (ref "IC15") (pin "E4") (pinfunction "FB1_E4") (pintype "input"))
      (node (ref "R55") (pin "1") (pinfunction "1_1") (pintype "passive"))
      (node (ref "R82") (pin "1") (pinfunction "1_1") (pintype "passive"))
    )
    (net (code "16") (name "Net-(IC15-FB2)") (class "Default")
      (node (ref "IC15") (pin "A4") (pinfunction "FB2_A4") (pintype "input"))
      (node (ref "R84") (pin "1") (pinfunction "1_1") (pintype "passive"))
    )
    (net (code "17") (name "Net-(IC15-FREQ)") (class "Default")
      (node (ref "IC15") (pin "C4") (pinfunction "FREQ_C4") (pintype "input"))
      (node (ref "TP2") (pin "1") (pinfunction "1_1") (pintype "bidirectional"))
    )
    (net (code "18") (name "Net-(IC15-INTVCC)") (class "Default")
      (node (ref "IC15") (pin "C3") (pinfunction "INTVCC_C3") (pintype "input"))
      (node (ref "TP1") (pin "1") (pinfunction "1_1") (pintype "bidirectional"))
    )
    (net (code "19") (name "Net-(IC15-RUN1)") (class "Default")
      (node (ref "IC15") (pin "B2") (pinfunction "RUN2_B2") (pintype "input"))
      (node (ref "IC15") (pin "D2") (pinfunction "RUN1_D2") (pintype "input"))
      (node (ref "R120") (pin "2") (pinfunction "2_2") (pintype "passive"))
      (node (ref "R123") (pin "2") (pinfunction "2_2") (pintype "passive"))
    )
    (net (code "20") (name "Net-(IC15-TRACK{slash}SS1)") (class "Default")
      (node (ref "C67") (pin "2") (pinfunction "2_2") (pintype "passive"))
      (node (ref "IC15") (pin "A3") (pinfunction "TRACK/SS2_A3") (pintype "input"))
      (node (ref "IC15") (pin "E3") (pinfunction "TRACK/SS1_E3") (pintype "input"))
    )
    (net (code "21") (name "Net-(IC15-VOUT1_1)") (class "Default")
      (node (ref "C73") (pin "2") (pinfunction "2_2") (pintype "passive"))
      (node (ref "IC15") (pin "D1") (pinfunction "VOUT1_1_D1") (pintype "power_in"))
      (node (ref "IC15") (pin "E1") (pinfunction "VOUT1_2_E1") (pintype "power_in"))
      (node (ref "L2") (pin "1") (pinfunction "1_1") (pintype "passive"))
    )
    (net (code "22") (name "Net-(IC15-VOUT2_1)") (class "Default")
      (node (ref "C161") (pin "2") (pinfunction "2_2") (pintype "passive"))
      (node (ref "IC15") (pin "A1") (pinfunction "VOUT2_1_A1") (pintype "power_in"))
      (node (ref "IC15") (pin "B1") (pinfunction "VOUT2_2_B1") (pintype "power_in"))
      (node (ref "L3") (pin "1") (pinfunction "1_1") (pintype "passive"))
    )
    (net (code "23") (name "Net-(IC18-FB)") (class "Default")
      (node (ref "IC18") (pin "16") (pinfunction "FB_16") (pintype "input"))
      (node (ref "R129") (pin "1") (pinfunction "1_1") (pintype "passive"))
      (node (ref "R130") (pin "2") (pinfunction "2_2") (pintype "passive"))
    )
    (net (code "24") (name "Net-(IC20-ADJ)") (class "Default")
      (node (ref "IC20") (pin "4") (pinfunction "ADJ_4") (pintype "input"))
      (node (ref "R131") (pin "1") (pinfunction "1_1") (pintype "passive"))
      (node (ref "R132") (pin "2") (pinfunction "2_2") (pintype "passive"))
    )
    (net (code "25") (name "Net-(IC20-BYP)") (class "Default")
      (node (ref "C170") (pin "1") (pinfunction "1_1") (pintype "passive"))
      (node (ref "IC20") (pin "3") (pinfunction "BYP_3") (pintype "input"))
    )
    (net (code "26") (name "Net-(IC21-ADJ)") (class "Default")
      (node (ref "IC21") (pin "2") (pinfunction "ADJ_2") (pintype "input"))
      (node (ref "R133") (pin "1") (pinfunction "1_1") (pintype "passive"))
      (node (ref "R135") (pin "2") (pinfunction "2_2") (pintype "passive"))
    )
    (net (code "27") (name "Net-(IC21-BYP)") (class "Default")
      (node (ref "C175") (pin "1") (pinfunction "1_1") (pintype "passive"))
      (node (ref "IC21") (pin "4") (pinfunction "BYP_4") (pintype "passive"))
    )
    (net (code "28") (name "Net-(IC22-FB)") (class "Default")
      (node (ref "IC22") (pin "5") (pinfunction "FB_5") (pintype "input"))
      (node (ref "R134") (pin "1") (pinfunction "1_1") (pintype "passive"))
      (node (ref "R136") (pin "2") (pinfunction "2_2") (pintype "passive"))
    )
    (net (code "29") (name "Net-(IC22-SW)") (class "Default")
      (node (ref "IC22") (pin "9") (pinfunction "SW_9") (pintype "output"))
      (node (ref "L4") (pin "1") (pinfunction "1_1") (pintype "passive"))
    )
    (net (code "30") (name "Net-(LD1-A)") (class "Default")
      (node (ref "LD1") (pin "2") (pinfunction "A_2") (pintype "passive"))
      (node (ref "R5") (pin "1") (pinfunction "1_1") (pintype "passive"))
    )
    (net (code "31") (name "Net-(LD3-A)") (class "Default")
      (node (ref "LD3") (pin "2") (pinfunction "A_2") (pintype "passive"))
      (node (ref "R33") (pin "1") (pinfunction "1_1") (pintype "passive"))
    )
    (net (code "32") (name "Net-(LD4-A)") (class "Default")
      (node (ref "LD4") (pin "2") (pinfunction "A_2") (pintype "passive"))
      (node (ref "R115") (pin "1") (pinfunction "1_1") (pintype "passive"))
    )
    (net (code "33") (name "Net-(LD7B-A)") (class "Default")
      (node (ref "LD7") (pin "4") (pinfunction "A_4") (pintype "passive"))
      (node (ref "R143") (pin "1") (pinfunction "1_1") (pintype "passive"))
    )
    (net (code "34") (name "Net-(LD9-A)") (class "Default")
      (node (ref "LD9") (pin "2") (pinfunction "A_2") (pintype "passive"))
      (node (ref "R139") (pin "1") (pinfunction "1_1") (pintype "passive"))
    )
    (net (code "35") (name "Net-(LD10-A)") (class "Default")
      (node (ref "LD10") (pin "2") (pinfunction "A_2") (pintype "passive"))
      (node (ref "R116") (pin "1") (pinfunction "1_1") (pintype "passive"))
    )
    (net (code "36") (name "Net-(R84-Pad2)") (class "Default")
      (node (ref "R84") (pin "2") (pinfunction "2_2") (pintype "passive"))
      (node (ref "R87") (pin "1") (pinfunction "1_1") (pintype "passive"))
    )
    (net (code "37") (name "P1V8A") (class "Default")
      (node (ref "C169") (pin "2") (pinfunction "2_2") (pintype "passive"))
      (node (ref "IC18") (pin "1") (pinfunction "OUT_1") (pintype "power_in"))
      (node (ref "IC18") (pin "18") (pinfunction "OUT_18") (pintype "power_in"))
      (node (ref "IC18") (pin "19") (pinfunction "OUT_19") (pintype "power_in"))
      (node (ref "IC18") (pin "20") (pinfunction "OUT_20") (pintype "power_in"))
      (node (ref "R129") (pin "2") (pinfunction "2_2") (pintype "passive"))
      (node (ref "TP10") (pin "1") (pinfunction "1_1") (pintype "bidirectional"))
    )
    (net (code "38") (name "P2V0") (class "Default")
      (node (ref "C163") (pin "2") (pinfunction "2_2") (pintype "passive"))
      (node (ref "C167") (pin "1") (pinfunction "1_1") (pintype "passive"))
      (node (ref "C76") (pin "1") (pinfunction "1_1") (pintype "passive"))
      (node (ref "IC18") (pin "5") (pinfunction "IN_5") (pintype "input"))
      (node (ref "IC18") (pin "6") (pinfunction "IN_6") (pintype "input"))
      (node (ref "IC18") (pin "7") (pinfunction "IN_7") (pintype "input"))
      (node (ref "IC18") (pin "8") (pinfunction "IN_8") (pintype "input"))
      (node (ref "L3") (pin "2") (pinfunction "2_2") (pintype "passive"))
      (node (ref "TP11") (pin "1") (pinfunction "1_1") (pintype "bidirectional"))
    )
    (net (code "39") (name "P3V3") (class "Default")
      (node (ref "C166") (pin "2") (pinfunction "2_2") (pintype "passive"))
      (node (ref "IC11") (pin "1") (pinfunction "OUT_1") (pintype "power_in"))
      (node (ref "IC11") (pin "18") (pinfunction "OUT_18") (pintype "power_in"))
      (node (ref "IC11") (pin "19") (pinfunction "OUT_19") (pintype "power_in"))
      (node (ref "IC11") (pin "20") (pinfunction "OUT_20") (pintype "power_in"))
      (node (ref "R115") (pin "2") (pinfunction "2_2") (pintype "passive"))
      (node (ref "R118") (pin "2") (pinfunction "2_2") (pintype "passive"))
      (node (ref "TP12") (pin "1") (pinfunction "1_1") (pintype "bidirectional"))
    )
    (net (code "40") (name "P3V3A") (class "Default")
      (node (ref "C78") (pin "2") (pinfunction "2_2") (pintype "passive"))
      (node (ref "IC7") (pin "1") (pinfunction "OUT_1") (pintype "power_in"))
      (node (ref "IC7") (pin "18") (pinfunction "OUT_18") (pintype "power_in"))
      (node (ref "IC7") (pin "19") (pinfunction "OUT_19") (pintype "power_in"))
      (node (ref "IC7") (pin "20") (pinfunction "OUT_20") (pintype "power_in"))
      (node (ref "R23") (pin "2") (pinfunction "2_2") (pintype "passive"))
      (node (ref "TP13") (pin "1") (pinfunction "1_1") (pintype "bidirectional"))
    )
    (net (code "41") (name "P3V3_MP") (class "Default")
      (node (ref "C48") (pin "2") (pinfunction "2_2") (pintype "passive"))
      (node (ref "IC12") (pin "8") (pinfunction "+VS_8") (pintype "power_in"))
      (node (ref "R116") (pin "2") (pinfunction "2_2") (pintype "passive"))
      (node (ref "R120") (pin "1") (pinfunction "1_1") (pintype "passive"))
      (node (ref "R121") (pin "2") (pinfunction "2_2") (pintype "passive"))
      (node (ref "R122") (pin "2") (pinfunction "2_2") (pintype "passive"))
      (node (ref "R143") (pin "2") (pinfunction "2_2") (pintype "passive"))
      (node (ref "R53") (pin "2") (pinfunction "2_2") (pintype "passive"))
      (node (ref "TP14") (pin "1") (pinfunction "1_1") (pintype "bidirectional"))
    )
    (net (code "42") (name "P3V6") (class "Default")
      (node (ref "C160") (pin "1") (pinfunction "1_1") (pintype "passive"))
      (node (ref "C165") (pin "2") (pinfunction "2_2") (pintype "passive"))
      (node (ref "C168") (pin "2") (pinfunction "2_2") (pintype "passive"))
      (node (ref "C63") (pin "1") (pinfunction "1_1") (pintype "passive"))
      (node (ref "C74") (pin "1") (pinfunction "1_1") (pintype "passive"))
      (node (ref "C75") (pin "2") (pinfunction "2_2") (pintype "passive"))
      (node (ref "C77") (pin "2") (pinfunction "2_2") (pintype "passive"))
      (node (ref "IC11") (pin "10") (pinfunction "BIAS_10") (pintype "input"))
      (node (ref "IC11") (pin "11") (pinfunction "EN_11") (pintype "input"))
      (node (ref "IC11") (pin "5") (pinfunction "IN_5") (pintype "input"))
      (node (ref "IC11") (pin "6") (pinfunction "IN_6") (pintype "input"))
      (node (ref "IC11") (pin "7") (pinfunction "IN_7") (pintype "input"))
      (node (ref "IC11") (pin "8") (pinfunction "IN_8") (pintype "input"))
      (node (ref "IC18") (pin "10") (pinfunction "BIAS_10") (pintype "input"))
      (node (ref "IC18") (pin "11") (pinfunction "EN_11") (pintype "input"))
      (node (ref "IC7") (pin "10") (pinfunction "BIAS_10") (pintype "input"))
      (node (ref "IC7") (pin "11") (pinfunction "EN_11") (pintype "input"))
      (node (ref "IC7") (pin "5") (pinfunction "IN_5") (pintype "input"))
      (node (ref "IC7") (pin "6") (pinfunction "IN_6") (pintype "input"))
      (node (ref "IC7") (pin "7") (pinfunction "IN_7") (pintype "input"))
      (node (ref "IC7") (pin "8") (pinfunction "IN_8") (pintype "input"))
      (node (ref "L2") (pin "2") (pinfunction "2_2") (pintype "passive"))
      (node (ref "R5") (pin "2") (pinfunction "2_2") (pintype "passive"))
      (node (ref "TP15") (pin "1") (pinfunction "1_1") (pintype "bidirectional"))
    )
    (net (code "43") (name "P5V0A") (class "Default")
      (node (ref "C170") (pin "2") (pinfunction "2_2") (pintype "passive"))
      (node (ref "C173") (pin "2") (pinfunction "2_2") (pintype "passive"))
      (node (ref "C79") (pin "1") (pinfunction "1_1") (pintype "passive"))
      (node (ref "IC20") (pin "5") (pinfunction "OUT_5") (pintype "power_in"))
      (node (ref "R131") (pin "2") (pinfunction "2_2") (pintype "passive"))
      (node (ref "R139") (pin "2") (pinfunction "2_2") (pintype "passive"))
      (node (ref "TP16") (pin "1") (pinfunction "1_1") (pintype "bidirectional"))
    )
    (net (code "44") (name "P7V0A") (class "Default")
      (node (ref "C155") (pin "1") (pinfunction "1_1") (pintype "passive"))
      (node (ref "C175") (pin "2") (pinfunction "2_2") (pintype "passive"))
      (node (ref "C177") (pin "2") (pinfunction "2_2") (pintype "passive"))
      (node (ref "IC21") (pin "1") (pinfunction "OUT_1") (pintype "power_in"))
      (node (ref "R133") (pin "2") (pinfunction "2_2") (pintype "passive"))
      (node (ref "TP17") (pin "1") (pinfunction "1_1") (pintype "bidirectional"))
    )
    (net (code "45") (name "P7V5") (class "Default")
      (node (ref "C178") (pin "2") (pinfunction "2_2") (pintype "passive"))
      (node (ref "C179") (pin "2") (pinfunction "2_2") (pintype "passive"))
      (node (ref "IC22") (pin "10") (pinfunction "VOS_10") (pintype "input"))
      (node (ref "IC22") (pin "8") (pinfunction "SLEEP_8") (pintype "input"))
      (node (ref "L4") (pin "2") (pinfunction "2_2") (pintype "passive"))
      (node (ref "L5") (pin "1") (pinfunction "1_1") (pintype "passive"))
      (node (ref "R134") (pin "2") (pinfunction "2_2") (pintype "passive"))
    )
    (net (code "46") (name "P7V5A") (class "Default")
      (node (ref "C156") (pin "1") (pinfunction "1_1") (pintype "passive"))
      (node (ref "C171") (pin "2") (pinfunction "2_2") (pintype "passive"))
      (node (ref "C174") (pin "2") (pinfunction "2_2") (pintype "passive"))
      (node (ref "C183") (pin "2") (pinfunction "2_2") (pintype "passive"))
      (node (ref "IC20") (pin "1") (pinfunction "IN_1") (pintype "input"))
      (node (ref "IC21") (pin "5") (pinfunction "~{SHDN}_5") (pintype "input"))
      (node (ref "IC21") (pin "8") (pinfunction "IN_8") (pintype "input"))
      (node (ref "L5") (pin "2") (pinfunction "2_2") (pintype "passive"))
    )
    (net (code "47") (name "P12V0") (class "Default")
      (node (ref "C181") (pin "2") (pinfunction "2_2") (pintype "passive"))
      (node (ref "C182") (pin "2") (pinfunction "2_2") (pintype "passive"))
      (node (ref "C64") (pin "2") (pinfunction "2_2") (pintype "passive"))
      (node (ref "C70") (pin "2") (pinfunction "2_2") (pintype "passive"))
      (node (ref "IC15") (pin "A2") (pinfunction "VIN_1_A2") (pintype "power_in"))
      (node (ref "IC15") (pin "B3") (pinfunction "VIN_2_B3") (pintype "power_in"))
      (node (ref "IC15") (pin "D3") (pinfunction "VIN_3_D3") (pintype "power_in"))
      (node (ref "IC15") (pin "E2") (pinfunction "VIN_4_E2") (pintype "power_in"))
      (node (ref "IC22") (pin "2") (pinfunction "VIN_2") (pintype "input"))
      (node (ref "IC22") (pin "3") (pinfunction "EN_3") (pintype "input"))
      (node (ref "R33") (pin "2") (pinfunction "2_2") (pintype "passive"))
      (node (ref "TP18") (pin "1") (pinfunction "1_1") (pintype "bidirectional"))
    )
    (net (code "48") (name "unconnected-(IC7-NC-Pad2)") (class "Default")
      (node (ref "IC7") (pin "2") (pinfunction "NC_2") (pintype "passive+no_connect"))
    )
    (net (code "49") (name "unconnected-(IC7-NC-Pad3)") (class "Default")
      (node (ref "IC7") (pin "3") (pinfunction "NC_3") (pintype "passive+no_connect"))
    )
    (net (code "50") (name "unconnected-(IC7-NC-Pad4)") (class "Default")
      (node (ref "IC7") (pin "4") (pinfunction "NC_4") (pintype "passive+no_connect"))
    )
    (net (code "51") (name "unconnected-(IC7-NC-Pad13)") (class "Default")
      (node (ref "IC7") (pin "13") (pinfunction "NC_13") (pintype "passive+no_connect"))
    )
    (net (code "52") (name "unconnected-(IC7-NC-Pad14)") (class "Default")
      (node (ref "IC7") (pin "14") (pinfunction "NC_14") (pintype "passive+no_connect"))
    )
    (net (code "53") (name "unconnected-(IC7-NC-Pad17)") (class "Default")
      (node (ref "IC7") (pin "17") (pinfunction "NC_17") (pintype "passive+no_connect"))
    )
    (net (code "54") (name "unconnected-(IC7-SS-Pad15)") (class "Default")
      (node (ref "IC7") (pin "15") (pinfunction "SS_15") (pintype "output+no_connect"))
    )
    (net (code "55") (name "unconnected-(IC11-NC-Pad2)") (class "Default")
      (node (ref "IC11") (pin "2") (pinfunction "NC_2") (pintype "passive+no_connect"))
    )
    (net (code "56") (name "unconnected-(IC11-NC-Pad3)") (class "Default")
      (node (ref "IC11") (pin "3") (pinfunction "NC_3") (pintype "passive+no_connect"))
    )
    (net (code "57") (name "unconnected-(IC11-NC-Pad4)") (class "Default")
      (node (ref "IC11") (pin "4") (pinfunction "NC_4") (pintype "passive+no_connect"))
    )
    (net (code "58") (name "unconnected-(IC11-NC-Pad13)") (class "Default")
      (node (ref "IC11") (pin "13") (pinfunction "NC_13") (pintype "passive+no_connect"))
    )
    (net (code "59") (name "unconnected-(IC11-NC-Pad14)") (class "Default")
      (node (ref "IC11") (pin "14") (pinfunction "NC_14") (pintype "passive+no_connect"))
    )
    (net (code "60") (name "unconnected-(IC11-NC-Pad17)") (class "Default")
      (node (ref "IC11") (pin "17") (pinfunction "NC_17") (pintype "passive+no_connect"))
    )
    (net (code "61") (name "unconnected-(IC11-SS-Pad15)") (class "Default")
      (node (ref "IC11") (pin "15") (pinfunction "SS_15") (pintype "output+no_connect"))
    )
    (net (code "62") (name "unconnected-(IC18-NC-Pad2)") (class "Default")
      (node (ref "IC18") (pin "2") (pinfunction "NC_2") (pintype "passive+no_connect"))
    )
    (net (code "63") (name "unconnected-(IC18-NC-Pad3)") (class "Default")
      (node (ref "IC18") (pin "3") (pinfunction "NC_3") (pintype "passive+no_connect"))
    )
    (net (code "64") (name "unconnected-(IC18-NC-Pad4)") (class "Default")
      (node (ref "IC18") (pin "4") (pinfunction "NC_4") (pintype "passive+no_connect"))
    )
    (net (code "65") (name "unconnected-(IC18-NC-Pad13)") (class "Default")
      (node (ref "IC18") (pin "13") (pinfunction "NC_13") (pintype "passive+no_connect"))
    )
    (net (code "66") (name "unconnected-(IC18-NC-Pad14)") (class "Default")
      (node (ref "IC18") (pin "14") (pinfunction "NC_14") (pintype "passive+no_connect"))
    )
    (net (code "67") (name "unconnected-(IC18-NC-Pad17)") (class "Default")
      (node (ref "IC18") (pin "17") (pinfunction "NC_17") (pintype "passive+no_connect"))
    )
    (net (code "68") (name "unconnected-(IC18-SS-Pad15)") (class "Default")
      (node (ref "IC18") (pin "15") (pinfunction "SS_15") (pintype "output+no_connect"))
    )
    (net (code "69") (name "unconnected-(IC22-NC-Pad4)") (class "Default")
      (node (ref "IC22") (pin "4") (pinfunction "NC_4") (pintype "passive"))
    )
  )
)
